# schema.net
KiCad netlist of a schematic drawn in EAGLE
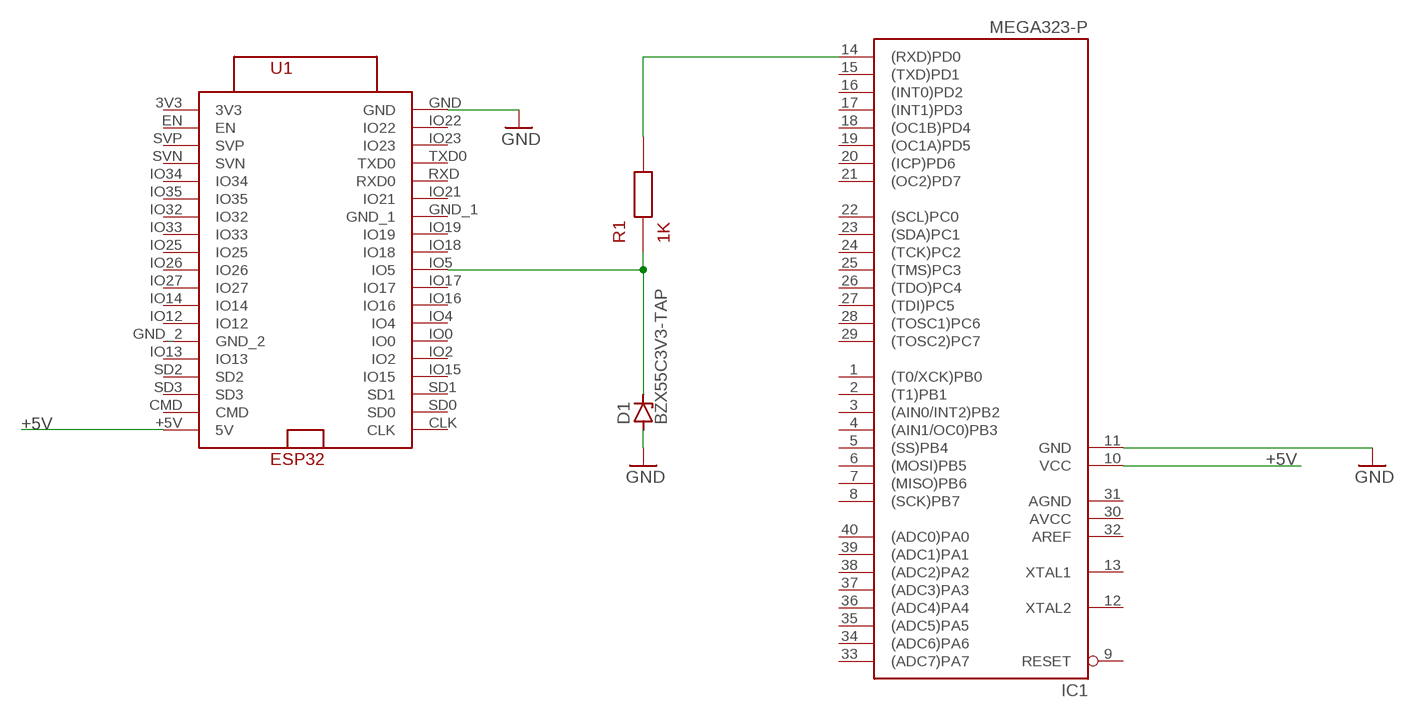
[diagram p0: schematic, sheet 1]

(export (version "E")
  (design (tool "Eeschema 10.0.6"))
  (components
    (comp (ref "D1")
      (value "BZX55C3V3-TAP")
      (footprint "eagle-import:DO35Z10")
      (libsource (lib "eagle-import") (part "BZX55"))
    )
    (comp (ref "IC1")
      (value "MEGA323-P")
      (footprint "eagle-import:DIL40")
      (libsource (lib "eagle-import") (part "MEGA323-P"))
    )
    (comp (ref "R1") (value "1K") (footprint "eagle-import:R") (libsource (lib "eagle-import") (part "R")))
    (comp (ref "U1")
      (value "ESP32")
      (footprint "eagle-import:ESP32")
      (libsource (lib "eagle-import") (part "ESP32"))
    )
  )
  (nets
    (net (code "1") (name "/+5V") (class "Default")
      (node (ref "IC1") (pin "10") (pinfunction "VCC_10") (pintype "power_in"))
      (node (ref "U1") (pin "+5V") (pinfunction "5V_+5V") (pintype "power_in"))
    )
    (net (code "2") (name "/3V3") (class "Default")
      (node (ref "U1") (pin "3V3") (pinfunction "3V3_3V3") (pintype "power_in"))
    )
    (net (code "3") (name "/AGND") (class "Default")
      (node (ref "IC1") (pin "31") (pinfunction "AGND_31") (pintype "power_in"))
    )
    (net (code "4") (name "/AVCC") (class "Default")
      (node (ref "IC1") (pin "30") (pinfunction "AVCC_30") (pintype "power_in"))
    )
    (net (code "5") (name "GND") (class "Default")
      (node (ref "D1") (pin "A") (pinfunction "A_A") (pintype "passive"))
      (node (ref "IC1") (pin "11") (pinfunction "GND_11") (pintype "power_in"))
      (node (ref "U1") (pin "GND") (pinfunction "GND_GND") (pintype "power_in"))
    )
    (net (code "6") (name "Net-(D1-PadC)") (class "Default")
      (node (ref "D1") (pin "C") (pinfunction "C_C") (pintype "passive"))
      (node (ref "R1") (pin "P$1") (pinfunction "P$1_P$1") (pintype "bidirectional"))
      (node (ref "U1") (pin "IO5") (pinfunction "IO5_IO5") (pintype "bidirectional"))
    )
    (net (code "7") (name "Net-(IC1-(RXD)PD0)") (class "Default")
      (node (ref "IC1") (pin "14") (pinfunction "(RXD)PD0_14") (pintype "bidirectional"))
      (node (ref "R1") (pin "P$2") (pinfunction "P$2_P$2") (pintype "bidirectional"))
    )
    (net (code "8") (name "unconnected-(IC1-(ADC0)PA0-Pad40)") (class "Default")
      (node (ref "IC1") (pin "40") (pinfunction "(ADC0)PA0_40") (pintype "bidirectional"))
    )
    (net (code "9") (name "unconnected-(IC1-(ADC1)PA1-Pad39)") (class "Default")
      (node (ref "IC1") (pin "39") (pinfunction "(ADC1)PA1_39") (pintype "bidirectional"))
    )
    (net (code "10") (name "unconnected-(IC1-(ADC2)PA2-Pad38)") (class "Default")
      (node (ref "IC1") (pin "38") (pinfunction "(ADC2)PA2_38") (pintype "bidirectional"))
    )
    (net (code "11") (name "unconnected-(IC1-(ADC3)PA3-Pad37)") (class "Default")
      (node (ref "IC1") (pin "37") (pinfunction "(ADC3)PA3_37") (pintype "bidirectional"))
    )
    (net (code "12") (name "unconnected-(IC1-(ADC4)PA4-Pad36)") (class "Default")
      (node (ref "IC1") (pin "36") (pinfunction "(ADC4)PA4_36") (pintype "bidirectional"))
    )
    (net (code "13") (name "unconnected-(IC1-(ADC5)PA5-Pad35)") (class "Default")
      (node (ref "IC1") (pin "35") (pinfunction "(ADC5)PA5_35") (pintype "bidirectional"))
    )
    (net (code "14") (name "unconnected-(IC1-(ADC6)PA6-Pad34)") (class "Default")
      (node (ref "IC1") (pin "34") (pinfunction "(ADC6)PA6_34") (pintype "bidirectional"))
    )
    (net (code "15") (name "unconnected-(IC1-(ADC7)PA7-Pad33)") (class "Default")
      (node (ref "IC1") (pin "33") (pinfunction "(ADC7)PA7_33") (pintype "bidirectional"))
    )
    (net (code "16") (name "unconnected-(IC1-(AIN0{slash}INT2)PB2-Pad3)") (class "Default")
      (node (ref "IC1") (pin "3") (pinfunction "(AIN0/INT2)PB2_3") (pintype "bidirectional"))
    )
    (net (code "17") (name "unconnected-(IC1-(AIN1{slash}OC0)PB3-Pad4)") (class "Default")
      (node (ref "IC1") (pin "4") (pinfunction "(AIN1/OC0)PB3_4") (pintype "bidirectional"))
    )
    (net (code "18") (name "unconnected-(IC1-(ICP)PD6-Pad20)") (class "Default")
      (node (ref "IC1") (pin "20") (pinfunction "(ICP)PD6_20") (pintype "bidirectional"))
    )
    (net (code "19") (name "unconnected-(IC1-(INT0)PD2-Pad16)") (class "Default")
      (node (ref "IC1") (pin "16") (pinfunction "(INT0)PD2_16") (pintype "bidirectional"))
    )
    (net (code "20") (name "unconnected-(IC1-(INT1)PD3-Pad17)") (class "Default")
      (node (ref "IC1") (pin "17") (pinfunction "(INT1)PD3_17") (pintype "bidirectional"))
    )
    (net (code "21") (name "unconnected-(IC1-(MISO)PB6-Pad7)") (class "Default")
      (node (ref "IC1") (pin "7") (pinfunction "(MISO)PB6_7") (pintype "bidirectional"))
    )
    (net (code "22") (name "unconnected-(IC1-(MOSI)PB5-Pad6)") (class "Default")
      (node (ref "IC1") (pin "6") (pinfunction "(MOSI)PB5_6") (pintype "bidirectional"))
    )
    (net (code "23") (name "unconnected-(IC1-(OC1A)PD5-Pad19)") (class "Default")
      (node (ref "IC1") (pin "19") (pinfunction "(OC1A)PD5_19") (pintype "bidirectional"))
    )
    (net (code "24") (name "unconnected-(IC1-(OC1B)PD4-Pad18)") (class "Default")
      (node (ref "IC1") (pin "18") (pinfunction "(OC1B)PD4_18") (pintype "bidirectional"))
    )
    (net (code "25") (name "unconnected-(IC1-(OC2)PD7-Pad21)") (class "Default")
      (node (ref "IC1") (pin "21") (pinfunction "(OC2)PD7_21") (pintype "bidirectional"))
    )
    (net (code "26") (name "unconnected-(IC1-(SCK)PB7-Pad8)") (class "Default")
      (node (ref "IC1") (pin "8") (pinfunction "(SCK)PB7_8") (pintype "bidirectional"))
    )
    (net (code "27") (name "unconnected-(IC1-(SCL)PC0-Pad22)") (class "Default")
      (node (ref "IC1") (pin "22") (pinfunction "(SCL)PC0_22") (pintype "bidirectional"))
    )
    (net (code "28") (name "unconnected-(IC1-(SDA)PC1-Pad23)") (class "Default")
      (node (ref "IC1") (pin "23") (pinfunction "(SDA)PC1_23") (pintype "bidirectional"))
    )
    (net (code "29") (name "unconnected-(IC1-(SS)PB4-Pad5)") (class "Default")
      (node (ref "IC1") (pin "5") (pinfunction "(SS)PB4_5") (pintype "bidirectional"))
    )
    (net (code "30") (name "unconnected-(IC1-(T0{slash}XCK)PB0-Pad1)") (class "Default")
      (node (ref "IC1") (pin "1") (pinfunction "(T0/XCK)PB0_1") (pintype "bidirectional"))
    )
    (net (code "31") (name "unconnected-(IC1-(T1)PB1-Pad2)") (class "Default")
      (node (ref "IC1") (pin "2") (pinfunction "(T1)PB1_2") (pintype "bidirectional"))
    )
    (net (code "32") (name "unconnected-(IC1-(TCK)PC2-Pad24)") (class "Default")
      (node (ref "IC1") (pin "24") (pinfunction "(TCK)PC2_24") (pintype "bidirectional"))
    )
    (net (code "33") (name "unconnected-(IC1-(TDI)PC5-Pad27)") (class "Default")
      (node (ref "IC1") (pin "27") (pinfunction "(TDI)PC5_27") (pintype "bidirectional"))
    )
    (net (code "34") (name "unconnected-(IC1-(TDO)PC4-Pad26)") (class "Default")
      (node (ref "IC1") (pin "26") (pinfunction "(TDO)PC4_26") (pintype "bidirectional"))
    )
    (net (code "35") (name "unconnected-(IC1-(TMS)PC3-Pad25)") (class "Default")
      (node (ref "IC1") (pin "25") (pinfunction "(TMS)PC3_25") (pintype "bidirectional"))
    )
    (net (code "36") (name "unconnected-(IC1-(TOSC1)PC6-Pad28)") (class "Default")
      (node (ref "IC1") (pin "28") (pinfunction "(TOSC1)PC6_28") (pintype "bidirectional"))
    )
    (net (code "37") (name "unconnected-(IC1-(TOSC2)PC7-Pad29)") (class "Default")
      (node (ref "IC1") (pin "29") (pinfunction "(TOSC2)PC7_29") (pintype "bidirectional"))
    )
    (net (code "38") (name "unconnected-(IC1-(TXD)PD1-Pad15)") (class "Default")
      (node (ref "IC1") (pin "15") (pinfunction "(TXD)PD1_15") (pintype "bidirectional"))
    )
    (net (code "39") (name "unconnected-(IC1-AREF-Pad32)") (class "Default")
      (node (ref "IC1") (pin "32") (pinfunction "AREF_32") (pintype "passive"))
    )
    (net (code "40") (name "unconnected-(IC1-RESET-Pad9)") (class "Default")
      (node (ref "IC1") (pin "9") (pinfunction "RESET_9") (pintype "input"))
    )
    (net (code "41") (name "unconnected-(IC1-XTAL1-Pad13)") (class "Default")
      (node (ref "IC1") (pin "13") (pinfunction "XTAL1_13") (pintype "bidirectional"))
    )
    (net (code "42") (name "unconnected-(IC1-XTAL2-Pad12)") (class "Default")
      (node (ref "IC1") (pin "12") (pinfunction "XTAL2_12") (pintype "bidirectional"))
    )
    (net (code "43") (name "unconnected-(U1-PadCLK)") (class "Default")
      (node (ref "U1") (pin "CLK") (pinfunction "CLK_CLK") (pintype "bidirectional"))
    )
    (net (code "44") (name "unconnected-(U1-PadCMD)") (class "Default")
      (node (ref "U1") (pin "CMD") (pinfunction "CMD_CMD") (pintype "bidirectional"))
    )
    (net (code "45") (name "unconnected-(U1-PadEN)") (class "Default")
      (node (ref "U1") (pin "EN") (pinfunction "EN_EN") (pintype "bidirectional"))
    )
    (net (code "46") (name "unconnected-(U1-PadGND_1)") (class "Default")
      (node (ref "U1") (pin "GND_1") (pinfunction "GND_1_GND_1") (pintype "bidirectional"))
    )
    (net (code "47") (name "unconnected-(U1-PadGND_2)") (class "Default")
      (node (ref "U1") (pin "GND_2") (pinfunction "GND_2_GND_2") (pintype "bidirectional"))
    )
    (net (code "48") (name "unconnected-(U1-PadIO0)") (class "Default")
      (node (ref "U1") (pin "IO0") (pinfunction "IO0_IO0") (pintype "bidirectional"))
    )
    (net (code "49") (name "unconnected-(U1-PadIO2)") (class "Default")
      (node (ref "U1") (pin "IO2") (pinfunction "IO2_IO2") (pintype "bidirectional"))
    )
    (net (code "50") (name "unconnected-(U1-PadIO4)") (class "Default")
      (node (ref "U1") (pin "IO4") (pinfunction "IO4_IO4") (pintype "bidirectional"))
    )
    (net (code "51") (name "unconnected-(U1-PadIO12)") (class "Default")
      (node (ref "U1") (pin "IO12") (pinfunction "IO12_IO12") (pintype "bidirectional"))
    )
    (net (code "52") (name "unconnected-(U1-PadIO13)") (class "Default")
      (node (ref "U1") (pin "IO13") (pinfunction "IO13_IO13") (pintype "bidirectional"))
    )
    (net (code "53") (name "unconnected-(U1-PadIO14)") (class "Default")
      (node (ref "U1") (pin "IO14") (pinfunction "IO14_IO14") (pintype "bidirectional"))
    )
    (net (code "54") (name "unconnected-(U1-PadIO15)") (class "Default")
      (node (ref "U1") (pin "IO15") (pinfunction "IO15_IO15") (pintype "bidirectional"))
    )
    (net (code "55") (name "unconnected-(U1-PadIO16)") (class "Default")
      (node (ref "U1") (pin "IO16") (pinfunction "IO16_IO16") (pintype "bidirectional"))
    )
    (net (code "56") (name "unconnected-(U1-PadIO17)") (class "Default")
      (node (ref "U1") (pin "IO17") (pinfunction "IO17_IO17") (pintype "bidirectional"))
    )
    (net (code "57") (name "unconnected-(U1-PadIO18)") (class "Default")
      (node (ref "U1") (pin "IO18") (pinfunction "IO18_IO18") (pintype "bidirectional"))
    )
    (net (code "58") (name "unconnected-(U1-PadIO19)") (class "Default")
      (node (ref "U1") (pin "IO19") (pinfunction "IO19_IO19") (pintype "bidirectional"))
    )
    (net (code "59") (name "unconnected-(U1-PadIO21)") (class "Default")
      (node (ref "U1") (pin "IO21") (pinfunction "IO21_IO21") (pintype "bidirectional"))
    )
    (net (code "60") (name "unconnected-(U1-PadIO22)") (class "Default")
      (node (ref "U1") (pin "IO22") (pinfunction "IO22_IO22") (pintype "bidirectional"))
    )
    (net (code "61") (name "unconnected-(U1-PadIO23)") (class "Default")
      (node (ref "U1") (pin "IO23") (pinfunction "IO23_IO23") (pintype "bidirectional"))
    )
    (net (code "62") (name "unconnected-(U1-PadIO25)") (class "Default")
      (node (ref "U1") (pin "IO25") (pinfunction "IO25_IO25") (pintype "bidirectional"))
    )
    (net (code "63") (name "unconnected-(U1-PadIO26)") (class "Default")
      (node (ref "U1") (pin "IO26") (pinfunction "IO26_IO26") (pintype "bidirectional"))
    )
    (net (code "64") (name "unconnected-(U1-PadIO27)") (class "Default")
      (node (ref "U1") (pin "IO27") (pinfunction "IO27_IO27") (pintype "bidirectional"))
    )
    (net (code "65") (name "unconnected-(U1-PadIO32)") (class "Default")
      (node (ref "U1") (pin "IO32") (pinfunction "IO32_IO32") (pintype "bidirectional"))
    )
    (net (code "66") (name "unconnected-(U1-PadIO33)") (class "Default")
      (node (ref "U1") (pin "IO33") (pinfunction "IO33_IO33") (pintype "bidirectional"))
    )
    (net (code "67") (name "unconnected-(U1-PadIO34)") (class "Default")
      (node (ref "U1") (pin "IO34") (pinfunction "IO34_IO34") (pintype "bidirectional"))
    )
    (net (code "68") (name "unconnected-(U1-PadIO35)") (class "Default")
      (node (ref "U1") (pin "IO35") (pinfunction "IO35_IO35") (pintype "bidirectional"))
    )
    (net (code "69") (name "unconnected-(U1-PadSD0)") (class "Default")
      (node (ref "U1") (pin "SD0") (pinfunction "SD0_SD0") (pintype "bidirectional"))
    )
    (net (code "70") (name "unconnected-(U1-PadSD1)") (class "Default")
      (node (ref "U1") (pin "SD1") (pinfunction "SD1_SD1") (pintype "bidirectional"))
    )
    (net (code "71") (name "unconnected-(U1-PadSD2)") (class "Default")
      (node (ref "U1") (pin "SD2") (pinfunction "SD2_SD2") (pintype "bidirectional"))
    )
    (net (code "72") (name "unconnected-(U1-PadSD3)") (class "Default")
      (node (ref "U1") (pin "SD3") (pinfunction "SD3_SD3") (pintype "bidirectional"))
    )
    (net (code "73") (name "unconnected-(U1-PadSVN)") (class "Default")
      (node (ref "U1") (pin "SVN") (pinfunction "SVN_SVN") (pintype "bidirectional"))
    )
    (net (code "74") (name "unconnected-(U1-PadSVP)") (class "Default")
      (node (ref "U1") (pin "SVP") (pinfunction "SVP_SVP") (pintype "bidirectional"))
    )
    (net (code "75") (name "unconnected-(U1-PadTXD0)") (class "Default")
      (node (ref "U1") (pin "TXD0") (pinfunction "TXD0_TXD0") (pintype "bidirectional"))
    )
    (net (code "76") (name "unconnected-(U1-RXD0-PadRXD)") (class "Default")
      (node (ref "U1") (pin "RXD") (pinfunction "RXD0_RXD") (pintype "bidirectional"))
    )
  )
)
